# PCB.net
KiCad netlist of a schematic drawn in EAGLE
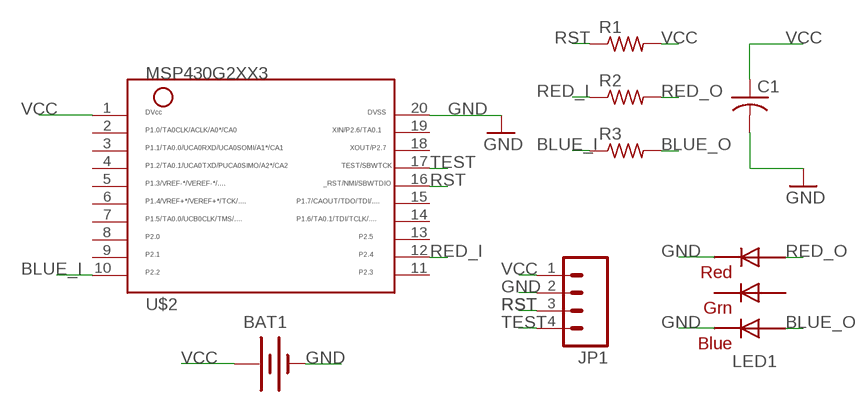
[diagram p0: schematic, sheet 1]

(export (version "E")
  (design (tool "Eeschema 10.0.6"))
  (components
    (comp (ref "BAT1")
      (value "BATTERYBU2032SM")
      (footprint "eagle-import:BU2032SM")
      (libsource (lib "eagle-import") (part "BATTERYBU2032SM"))
    )
    (comp (ref "C1")
      (value "C-USC1206")
      (footprint "eagle-import:C1206")
      (libsource (lib "eagle-import") (part "C-USC1206"))
    )
    (comp (ref "JP1")
      (value "M04LOCK")
      (footprint "eagle-import:1X04_LOCK")
      (libsource (lib "eagle-import") (part "M04LOCK"))
    )
    (comp (ref "LED1")
      (value "RGBLED5050")
      (footprint "eagle-import:RGBLED5050")
      (libsource (lib "eagle-import") (part "RGBLED5050"))
    )
    (comp (ref "R1")
      (value "R-US_R1206")
      (footprint "eagle-import:R1206")
      (libsource (lib "eagle-import") (part "R-US_R1206"))
    )
    (comp (ref "R2")
      (value "R-US_R1206")
      (footprint "eagle-import:R1206")
      (libsource (lib "eagle-import") (part "R-US_R1206"))
    )
    (comp (ref "R3")
      (value "R-US_R1206")
      (footprint "eagle-import:R1206")
      (libsource (lib "eagle-import") (part "R-US_R1206"))
    )
    (comp (ref "U$2")
      (value "MSP430G2XX3TSSOP")
      (footprint "eagle-import:PW20")
      (libsource (lib "eagle-import") (part "MSP430G2XX3TSSOP"))
    )
  )
  (nets
    (net (code "1") (name "/BLUE_I") (class "Default")
      (node (ref "R3") (pin "1") (pinfunction "1_1") (pintype "passive"))
      (node (ref "U$2") (pin "10") (pinfunction "10_10") (pintype "bidirectional"))
    )
    (net (code "2") (name "/BLUE_O") (class "Default")
      (node (ref "LED1") (pin "3") (pinfunction "BLUE_A_3") (pintype "bidirectional"))
      (node (ref "R3") (pin "2") (pinfunction "2_2") (pintype "passive"))
    )
    (net (code "3") (name "/RED_I") (class "Default")
      (node (ref "R2") (pin "1") (pinfunction "1_1") (pintype "passive"))
      (node (ref "U$2") (pin "12") (pinfunction "12_12") (pintype "bidirectional"))
    )
    (net (code "4") (name "/RED_O") (class "Default")
      (node (ref "LED1") (pin "2") (pinfunction "RED_A_2") (pintype "bidirectional"))
      (node (ref "R2") (pin "2") (pinfunction "2_2") (pintype "passive"))
    )
    (net (code "5") (name "/RST") (class "Default")
      (node (ref "JP1") (pin "3") (pinfunction "3_3") (pintype "passive"))
      (node (ref "R1") (pin "1") (pinfunction "1_1") (pintype "passive"))
      (node (ref "U$2") (pin "16") (pinfunction "16_16") (pintype "bidirectional"))
    )
    (net (code "6") (name "/TEST") (class "Default")
      (node (ref "JP1") (pin "4") (pinfunction "4_4") (pintype "passive"))
      (node (ref "U$2") (pin "17") (pinfunction "17_17") (pintype "bidirectional"))
    )
    (net (code "7") (name "/VCC") (class "Default")
      (node (ref "BAT1") (pin "P$1") (pinfunction "+_P$1") (pintype "power_in"))
      (node (ref "C1") (pin "1") (pinfunction "1_1") (pintype "passive"))
      (node (ref "JP1") (pin "1") (pinfunction "1_1") (pintype "passive"))
      (node (ref "R1") (pin "2") (pinfunction "2_2") (pintype "passive"))
      (node (ref "U$2") (pin "1") (pinfunction "1_1") (pintype "bidirectional"))
    )
    (net (code "8") (name "GND") (class "Default")
      (node (ref "BAT1") (pin "P$2") (pinfunction "-_P$2") (pintype "power_in"))
      (node (ref "C1") (pin "2") (pinfunction "2_2") (pintype "passive"))
      (node (ref "JP1") (pin "2") (pinfunction "2_2") (pintype "passive"))
      (node (ref "LED1") (pin "4") (pinfunction "BLUE_C_4") (pintype "bidirectional"))
      (node (ref "LED1") (pin "5") (pinfunction "RED_C_5") (pintype "bidirectional"))
      (node (ref "U$2") (pin "20") (pinfunction "20_20") (pintype "bidirectional"))
    )
    (net (code "9") (name "unconnected-(LED1-GREEN_A-Pad1)") (class "Default")
      (node (ref "LED1") (pin "1") (pinfunction "GREEN_A_1") (pintype "bidirectional"))
    )
    (net (code "10") (name "unconnected-(LED1-GREEN_C-Pad6)") (class "Default")
      (node (ref "LED1") (pin "6") (pinfunction "GREEN_C_6") (pintype "bidirectional"))
    )
    (net (code "11") (name "unconnected-(U$2-Pad2)") (class "Default")
      (node (ref "U$2") (pin "2") (pinfunction "2_2") (pintype "bidirectional"))
    )
    (net (code "12") (name "unconnected-(U$2-Pad3)") (class "Default")
      (node (ref "U$2") (pin "3") (pinfunction "3_3") (pintype "bidirectional"))
    )
    (net (code "13") (name "unconnected-(U$2-Pad4)") (class "Default")
      (node (ref "U$2") (pin "4") (pinfunction "4_4") (pintype "bidirectional"))
    )
    (net (code "14") (name "unconnected-(U$2-Pad5)") (class "Default")
      (node (ref "U$2") (pin "5") (pinfunction "5_5") (pintype "bidirectional"))
    )
    (net (code "15") (name "unconnected-(U$2-Pad6)") (class "Default")
      (node (ref "U$2") (pin "6") (pinfunction "6_6") (pintype "bidirectional"))
    )
    (net (code "16") (name "unconnected-(U$2-Pad7)") (class "Default")
      (node (ref "U$2") (pin "7") (pinfunction "7_7") (pintype "bidirectional"))
    )
    (net (code "17") (name "unconnected-(U$2-Pad8)") (class "Default")
      (node (ref "U$2") (pin "8") (pinfunction "8_8") (pintype "bidirectional"))
    )
    (net (code "18") (name "unconnected-(U$2-Pad9)") (class "Default")
      (node (ref "U$2") (pin "9") (pinfunction "9_9") (pintype "bidirectional"))
    )
    (net (code "19") (name "unconnected-(U$2-Pad11)") (class "Default")
      (node (ref "U$2") (pin "11") (pinfunction "11_11") (pintype "bidirectional"))
    )
    (net (code "20") (name "unconnected-(U$2-Pad13)") (class "Default")
      (node (ref "U$2") (pin "13") (pinfunction "13_13") (pintype "bidirectional"))
    )
    (net (code "21") (name "unconnected-(U$2-Pad14)") (class "Default")
      (node (ref "U$2") (pin "14") (pinfunction "14_14") (pintype "bidirectional"))
    )
    (net (code "22") (name "unconnected-(U$2-Pad15)") (class "Default")
      (node (ref "U$2") (pin "15") (pinfunction "15_15") (pintype "bidirectional"))
    )
    (net (code "23") (name "unconnected-(U$2-Pad18)") (class "Default")
      (node (ref "U$2") (pin "18") (pinfunction "18_18") (pintype "bidirectional"))
    )
    (net (code "24") (name "unconnected-(U$2-Pad19)") (class "Default")
      (node (ref "U$2") (pin "19") (pinfunction "19_19") (pintype "bidirectional"))
    )
  )
)
